# Desklamp_V322.net
KiCad netlist of a schematic drawn in EAGLE
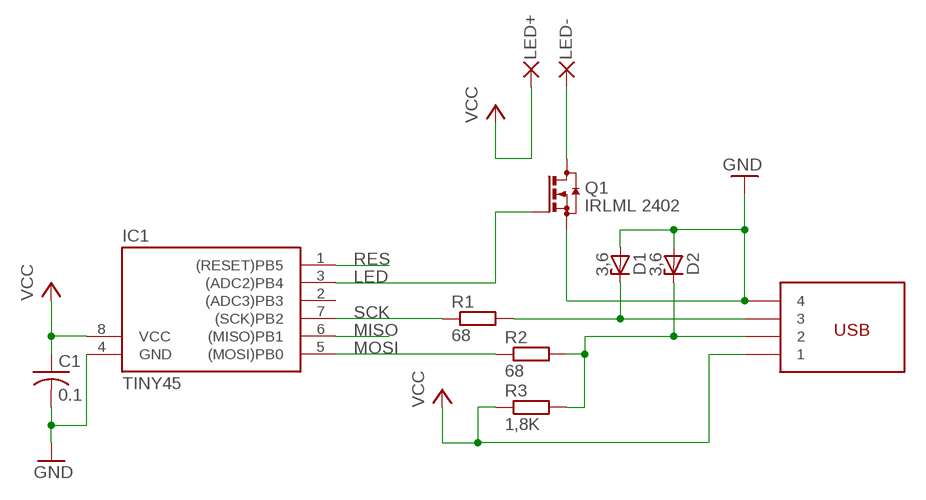
[diagram p0: schematic, sheet 1]

(export (version "E")
  (design (tool "Eeschema 10.0.6"))
  (components
    (comp (ref "C1")
      (value "0.1")
      (footprint "eagle-import:C0805")
      (libsource (lib "eagle-import") (part "C-USC0805"))
    )
    (comp (ref "D1")
      (value "3,6")
      (footprint "eagle-import:SOT23")
      (libsource (lib "eagle-import") (part "ZENER-DIODESOT23"))
    )
    (comp (ref "D2")
      (value "3,6")
      (footprint "eagle-import:SOT23")
      (libsource (lib "eagle-import") (part "ZENER-DIODESOT23"))
    )
    (comp (ref "IC1")
      (value "TINY45")
      (footprint "eagle-import:SOIC8")
      (libsource (lib "eagle-import") (part "TINY45"))
    )
    (comp (ref "PAD7")
      (value "LED+")
      (footprint "eagle-import:SMD1,27-2,54")
      (libsource (lib "eagle-import") (part "SMD2"))
    )
    (comp (ref "PAD8")
      (value "LED-")
      (footprint "eagle-import:SMD1,27-2,54")
      (libsource (lib "eagle-import") (part "SMD2"))
    )
    (comp (ref "Q1")
      (value "IRLML 2402")
      (footprint "eagle-import:SOT23")
      (libsource (lib "eagle-import") (part "BSS123"))
    )
    (comp (ref "R1")
      (value "68")
      (footprint "eagle-import:R0603")
      (libsource (lib "eagle-import") (part "R-EU_R0603"))
    )
    (comp (ref "R2")
      (value "68")
      (footprint "eagle-import:R0603")
      (libsource (lib "eagle-import") (part "R-EU_R0603"))
    )
    (comp (ref "R3")
      (value "1,8K")
      (footprint "eagle-import:R0603")
      (libsource (lib "eagle-import") (part "R-EU_R0603"))
    )
    (comp (ref "U$1")
      (value "USB_A_EDGE")
      (footprint "eagle-import:USB_A_EDGE")
      (libsource (lib "eagle-import") (part "USB_A_EDGE"))
    )
  )
  (nets
    (net (code "1") (name "/LED") (class "Default")
      (node (ref "IC1") (pin "3") (pinfunction "(ADC2)PB4_3") (pintype "bidirectional"))
      (node (ref "Q1") (pin "1") (pinfunction "G_1") (pintype "passive"))
    )
    (net (code "2") (name "/MISO") (class "Default")
      (node (ref "IC1") (pin "6") (pinfunction "(MISO)PB1_6") (pintype "bidirectional"))
    )
    (net (code "3") (name "/MOSI") (class "Default")
      (node (ref "IC1") (pin "5") (pinfunction "(MOSI)PB0_5") (pintype "bidirectional"))
      (node (ref "R2") (pin "1") (pinfunction "1_1") (pintype "passive"))
    )
    (net (code "4") (name "/RES") (class "Default")
      (node (ref "IC1") (pin "1") (pinfunction "(RESET)PB5_1") (pintype "bidirectional"))
    )
    (net (code "5") (name "/SCK") (class "Default")
      (node (ref "IC1") (pin "7") (pinfunction "(SCK)PB2_7") (pintype "bidirectional"))
      (node (ref "R1") (pin "1") (pinfunction "1_1") (pintype "passive"))
    )
    (net (code "6") (name "GND") (class "Default")
      (node (ref "C1") (pin "2") (pinfunction "2_2") (pintype "passive"))
      (node (ref "D1") (pin "1") (pinfunction "A_1") (pintype "passive"))
      (node (ref "D2") (pin "1") (pinfunction "A_1") (pintype "passive"))
      (node (ref "IC1") (pin "4") (pinfunction "GND_4") (pintype "power_in"))
      (node (ref "Q1") (pin "2") (pinfunction "S_2") (pintype "passive"))
      (node (ref "U$1") (pin "P$3") (pinfunction "4_P$3") (pintype "bidirectional"))
    )
    (net (code "7") (name "Net-(D1-C)") (class "Default")
      (node (ref "D1") (pin "3") (pinfunction "C_3") (pintype "passive"))
      (node (ref "R1") (pin "2") (pinfunction "2_2") (pintype "passive"))
      (node (ref "U$1") (pin "P$1") (pinfunction "3_P$1") (pintype "bidirectional"))
    )
    (net (code "8") (name "Net-(D2-C)") (class "Default")
      (node (ref "D2") (pin "3") (pinfunction "C_3") (pintype "passive"))
      (node (ref "R2") (pin "2") (pinfunction "2_2") (pintype "passive"))
      (node (ref "R3") (pin "2") (pinfunction "2_2") (pintype "passive"))
      (node (ref "U$1") (pin "P$2") (pinfunction "2_P$2") (pintype "bidirectional"))
    )
    (net (code "9") (name "Net-(PAD8-P)") (class "Default")
      (node (ref "PAD8") (pin "1") (pinfunction "P_1") (pintype "passive"))
      (node (ref "Q1") (pin "3") (pinfunction "D_3") (pintype "passive"))
    )
    (net (code "10") (name "VCC") (class "Default")
      (node (ref "C1") (pin "1") (pinfunction "1_1") (pintype "passive"))
      (node (ref "IC1") (pin "8") (pinfunction "VCC_8") (pintype "power_in"))
      (node (ref "PAD7") (pin "1") (pinfunction "P_1") (pintype "passive"))
      (node (ref "R3") (pin "1") (pinfunction "1_1") (pintype "passive"))
      (node (ref "U$1") (pin "P$4") (pinfunction "1_P$4") (pintype "bidirectional"))
    )
    (net (code "11") (name "unconnected-(IC1-(ADC3)PB3-Pad2)") (class "Default")
      (node (ref "IC1") (pin "2") (pinfunction "(ADC3)PB3_2") (pintype "bidirectional"))
    )
  )
)
